# protomega.net
KiCad netlist of a schematic drawn in EAGLE
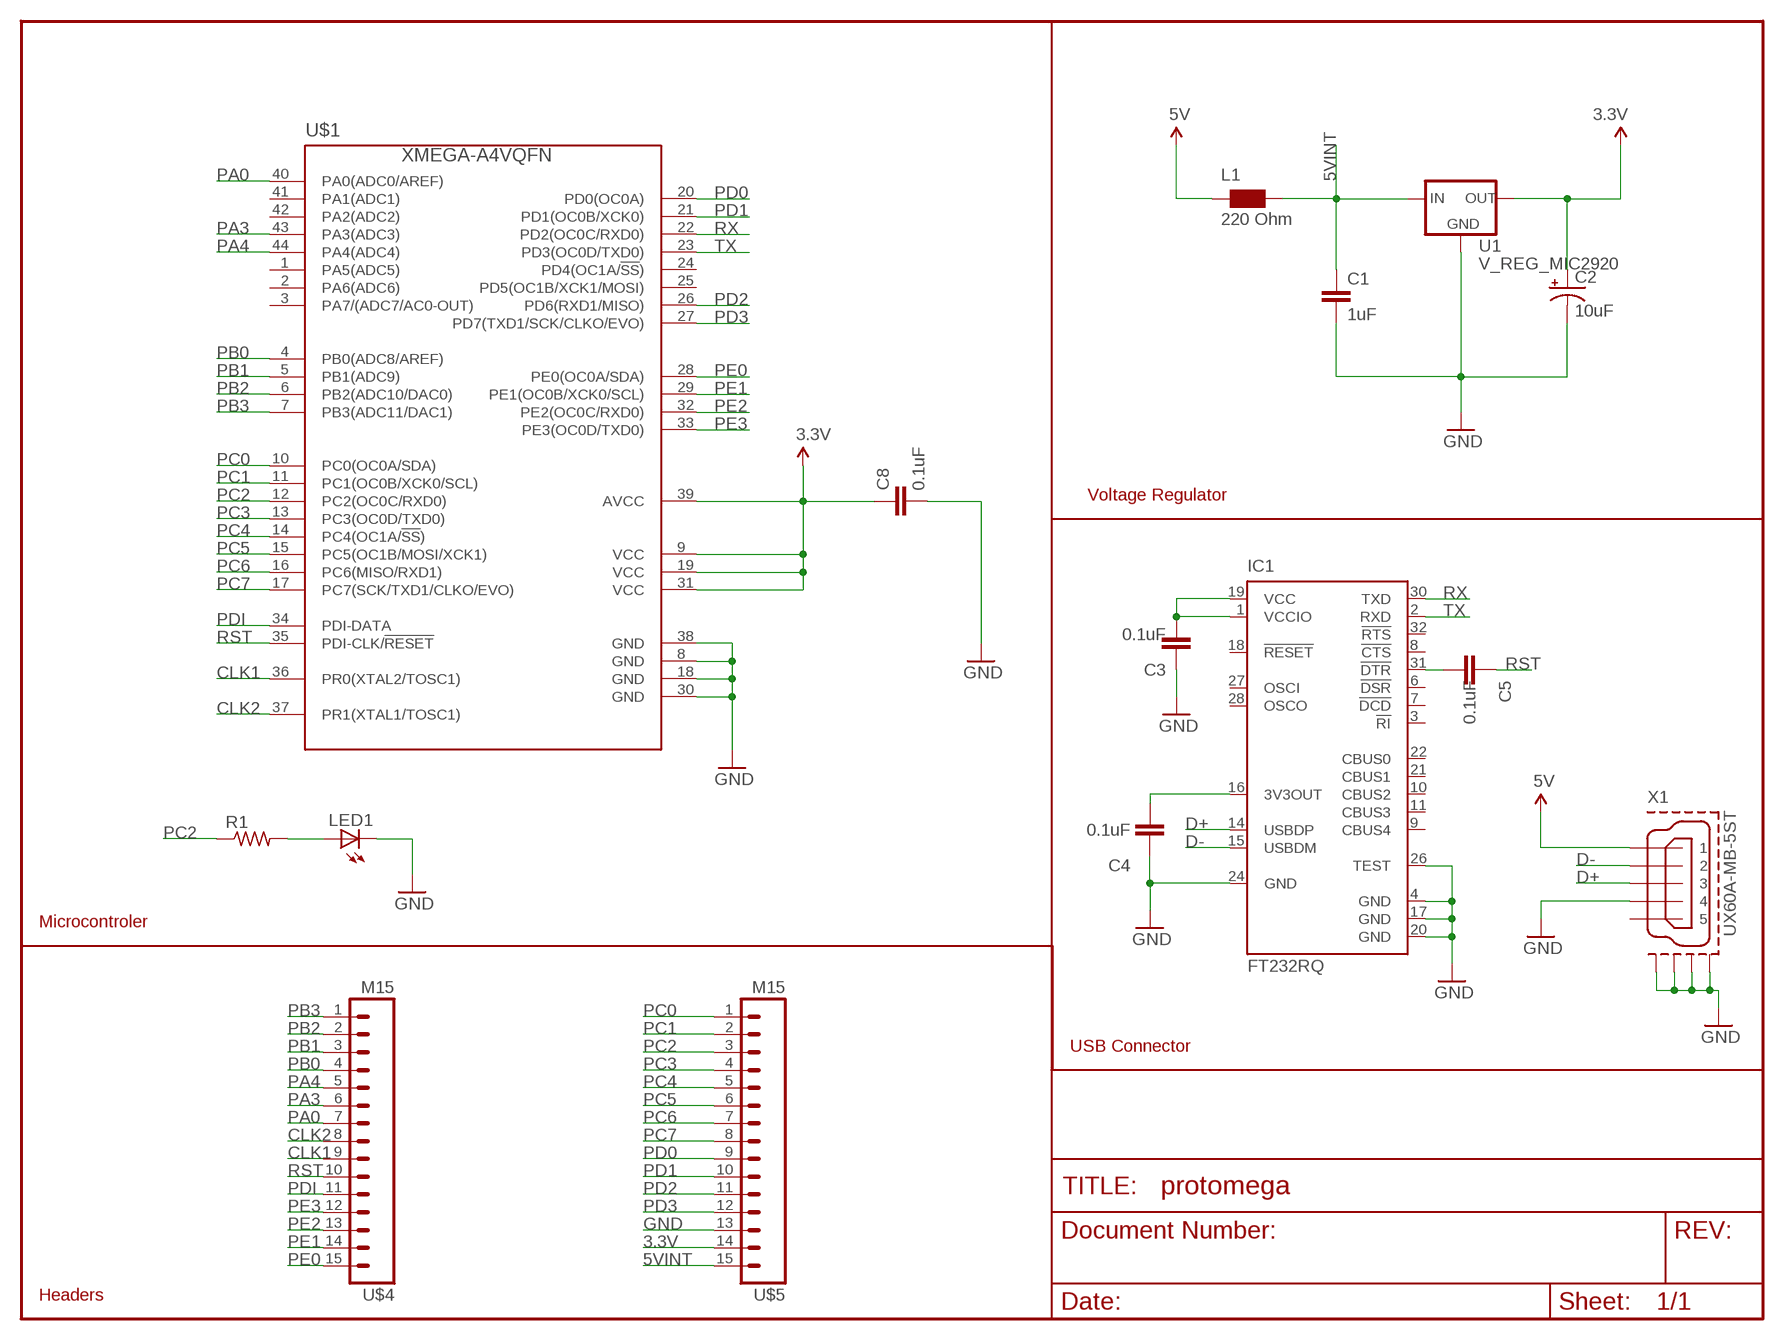
[diagram p0: schematic, sheet 1]

(export (version "E")
  (design (tool "Eeschema 10.0.6"))
  (components
    (comp (ref "C1")
      (value "1uF")
      (footprint "eagle-import:C0603")
      (libsource (lib "eagle-import") (part "C-EUC0603"))
    )
    (comp (ref "C2")
      (value "10uF")
      (footprint "eagle-import:EIA3216")
      (libsource (lib "eagle-import") (part "CAP_POL1206"))
    )
    (comp (ref "C3")
      (value "0.1uF")
      (footprint "eagle-import:C0603")
      (libsource (lib "eagle-import") (part "C-EUC0603"))
    )
    (comp (ref "C4")
      (value "0.1uF")
      (footprint "eagle-import:C0603")
      (libsource (lib "eagle-import") (part "C-EUC0603"))
    )
    (comp (ref "C5")
      (value "0.1uF")
      (footprint "eagle-import:C0603")
      (libsource (lib "eagle-import") (part "C-EUC0603"))
    )
    (comp (ref "C8")
      (value "0.1uF")
      (footprint "eagle-import:C0603")
      (libsource (lib "eagle-import") (part "C-EUC0603"))
    )
    (comp (ref "IC1")
      (value "FT232RQ")
      (footprint "eagle-import:QFN32")
      (libsource (lib "eagle-import") (part "FT232RQ"))
    )
    (comp (ref "L1")
      (value "220 Ohm")
      (footprint "eagle-import:0603")
      (libsource (lib "eagle-import") (part "WE-CBF_0603"))
    )
    (comp (ref "LED1")
      (value "LEDSMT1206")
      (footprint "eagle-import:1206")
      (libsource (lib "eagle-import") (part "LEDSMT1206"))
    )
    (comp (ref "R1")
      (value "R-US_R0603")
      (footprint "eagle-import:R0603")
      (libsource (lib "eagle-import") (part "R-US_R0603"))
    )
    (comp (ref "U$1")
      (value "XMEGA-A4VQFN")
      (footprint "eagle-import:QFN44")
      (libsource (lib "eagle-import") (part "XMEGA-A4VQFN"))
    )
    (comp (ref "U$4")
      (value "M15")
      (footprint "eagle-import:1X15")
      (libsource (lib "eagle-import") (part "M15"))
    )
    (comp (ref "U$5")
      (value "M15")
      (footprint "eagle-import:1X15")
      (libsource (lib "eagle-import") (part "M15"))
    )
    (comp (ref "U1")
      (value "V_REG_MIC2920")
      (footprint "eagle-import:SOT223")
      (libsource (lib "eagle-import") (part "V_REG_MIC2920"))
    )
    (comp (ref "X1")
      (value "UX60A-MB-5ST")
      (footprint "eagle-import:UX60A-MB-5ST")
      (libsource (lib "eagle-import") (part "MINI-USB-SHIELD-UX60A-MB-5ST"))
    )
  )
  (nets
    (net (code "1") (name "/5VINT") (class "Default")
      (node (ref "C1") (pin "1") (pinfunction "1_1") (pintype "passive"))
      (node (ref "L1") (pin "2") (pinfunction "2_2") (pintype "passive"))
      (node (ref "U$5") (pin "15") (pinfunction "15_15") (pintype "passive"))
      (node (ref "U1") (pin "1") (pinfunction "IN_1") (pintype "input"))
    )
    (net (code "2") (name "/CLK1") (class "Default")
      (node (ref "U$1") (pin "36") (pinfunction "PR0(XTAL2/TOSC1)_36") (pintype "bidirectional"))
      (node (ref "U$4") (pin "9") (pinfunction "9_9") (pintype "passive"))
    )
    (net (code "3") (name "/CLK2") (class "Default")
      (node (ref "U$1") (pin "37") (pinfunction "PR1(XTAL1/TOSC1)_37") (pintype "bidirectional"))
      (node (ref "U$4") (pin "8") (pinfunction "8_8") (pintype "passive"))
    )
    (net (code "4") (name "/D+") (class "Default")
      (node (ref "IC1") (pin "14") (pinfunction "USBDP_14") (pintype "bidirectional"))
      (node (ref "X1") (pin "3") (pinfunction "3_3") (pintype "input"))
    )
    (net (code "5") (name "/D-") (class "Default")
      (node (ref "IC1") (pin "15") (pinfunction "USBDM_15") (pintype "bidirectional"))
      (node (ref "X1") (pin "2") (pinfunction "2_2") (pintype "input"))
    )
    (net (code "6") (name "/PA0") (class "Default")
      (node (ref "U$1") (pin "40") (pinfunction "PA0(ADC0/AREF)_40") (pintype "bidirectional"))
      (node (ref "U$4") (pin "7") (pinfunction "7_7") (pintype "passive"))
    )
    (net (code "7") (name "/PA3") (class "Default")
      (node (ref "U$1") (pin "43") (pinfunction "PA3(ADC3)_43") (pintype "bidirectional"))
      (node (ref "U$4") (pin "6") (pinfunction "6_6") (pintype "passive"))
    )
    (net (code "8") (name "/PA4") (class "Default")
      (node (ref "U$1") (pin "44") (pinfunction "PA4(ADC4)_44") (pintype "bidirectional"))
      (node (ref "U$4") (pin "5") (pinfunction "5_5") (pintype "passive"))
    )
    (net (code "9") (name "/PB0") (class "Default")
      (node (ref "U$1") (pin "4") (pinfunction "PB0(ADC8/AREF)_4") (pintype "bidirectional"))
      (node (ref "U$4") (pin "4") (pinfunction "4_4") (pintype "passive"))
    )
    (net (code "10") (name "/PB1") (class "Default")
      (node (ref "U$1") (pin "5") (pinfunction "PB1(ADC9)_5") (pintype "bidirectional"))
      (node (ref "U$4") (pin "3") (pinfunction "3_3") (pintype "passive"))
    )
    (net (code "11") (name "/PB2") (class "Default")
      (node (ref "U$1") (pin "6") (pinfunction "PB2(ADC10/DAC0)_6") (pintype "bidirectional"))
      (node (ref "U$4") (pin "2") (pinfunction "2_2") (pintype "passive"))
    )
    (net (code "12") (name "/PB3") (class "Default")
      (node (ref "U$1") (pin "7") (pinfunction "PB3(ADC11/DAC1)_7") (pintype "bidirectional"))
      (node (ref "U$4") (pin "1") (pinfunction "1_1") (pintype "passive"))
    )
    (net (code "13") (name "/PC0") (class "Default")
      (node (ref "U$1") (pin "10") (pinfunction "PC0(OC0A/SDA)_10") (pintype "bidirectional"))
      (node (ref "U$5") (pin "1") (pinfunction "1_1") (pintype "passive"))
    )
    (net (code "14") (name "/PC1") (class "Default")
      (node (ref "U$1") (pin "11") (pinfunction "PC1(OC0B/XCK0/SCL)_11") (pintype "bidirectional"))
      (node (ref "U$5") (pin "2") (pinfunction "2_2") (pintype "passive"))
    )
    (net (code "15") (name "/PC2") (class "Default")
      (node (ref "R1") (pin "1") (pinfunction "1_1") (pintype "passive"))
      (node (ref "U$1") (pin "12") (pinfunction "PC2(OC0C/RXD0)_12") (pintype "bidirectional"))
      (node (ref "U$5") (pin "3") (pinfunction "3_3") (pintype "passive"))
    )
    (net (code "16") (name "/PC3") (class "Default")
      (node (ref "U$1") (pin "13") (pinfunction "PC3(OC0D/TXD0)_13") (pintype "bidirectional"))
      (node (ref "U$5") (pin "4") (pinfunction "4_4") (pintype "passive"))
    )
    (net (code "17") (name "/PC4") (class "Default")
      (node (ref "U$1") (pin "14") (pinfunction "PC4(OC1A/~{SS})_14") (pintype "bidirectional"))
      (node (ref "U$5") (pin "5") (pinfunction "5_5") (pintype "passive"))
    )
    (net (code "18") (name "/PC5") (class "Default")
      (node (ref "U$1") (pin "15") (pinfunction "PC5(OC1B/MOSI/XCK1)_15") (pintype "bidirectional"))
      (node (ref "U$5") (pin "6") (pinfunction "6_6") (pintype "passive"))
    )
    (net (code "19") (name "/PC6") (class "Default")
      (node (ref "U$1") (pin "16") (pinfunction "PC6(MISO/RXD1)_16") (pintype "bidirectional"))
      (node (ref "U$5") (pin "7") (pinfunction "7_7") (pintype "passive"))
    )
    (net (code "20") (name "/PC7") (class "Default")
      (node (ref "U$1") (pin "17") (pinfunction "PC7(SCK/TXD1/CLKO/EVO)_17") (pintype "bidirectional"))
      (node (ref "U$5") (pin "8") (pinfunction "8_8") (pintype "passive"))
    )
    (net (code "21") (name "/PD0") (class "Default")
      (node (ref "U$1") (pin "20") (pinfunction "PD0(OC0A)_20") (pintype "bidirectional"))
      (node (ref "U$5") (pin "9") (pinfunction "9_9") (pintype "passive"))
    )
    (net (code "22") (name "/PD1") (class "Default")
      (node (ref "U$1") (pin "21") (pinfunction "PD1(OC0B/XCK0)_21") (pintype "bidirectional"))
      (node (ref "U$5") (pin "10") (pinfunction "10_10") (pintype "passive"))
    )
    (net (code "23") (name "/PD2") (class "Default")
      (node (ref "U$1") (pin "26") (pinfunction "PD6(RXD1/MISO)_26") (pintype "bidirectional"))
      (node (ref "U$5") (pin "11") (pinfunction "11_11") (pintype "passive"))
    )
    (net (code "24") (name "/PD3") (class "Default")
      (node (ref "U$1") (pin "27") (pinfunction "PD7(TXD1/SCK/CLKO/EVO)_27") (pintype "bidirectional"))
      (node (ref "U$5") (pin "12") (pinfunction "12_12") (pintype "passive"))
    )
    (net (code "25") (name "/PDI") (class "Default")
      (node (ref "U$1") (pin "34") (pinfunction "PDI-DATA_34") (pintype "bidirectional"))
      (node (ref "U$4") (pin "11") (pinfunction "11_11") (pintype "passive"))
    )
    (net (code "26") (name "/PE0") (class "Default")
      (node (ref "U$1") (pin "28") (pinfunction "PE0(OC0A/SDA)_28") (pintype "bidirectional"))
      (node (ref "U$4") (pin "15") (pinfunction "15_15") (pintype "passive"))
    )
    (net (code "27") (name "/PE1") (class "Default")
      (node (ref "U$1") (pin "29") (pinfunction "PE1(OC0B/XCK0/SCL)_29") (pintype "bidirectional"))
      (node (ref "U$4") (pin "14") (pinfunction "14_14") (pintype "passive"))
    )
    (net (code "28") (name "/PE2") (class "Default")
      (node (ref "U$1") (pin "32") (pinfunction "PE2(OC0C/RXD0)_32") (pintype "bidirectional"))
      (node (ref "U$4") (pin "13") (pinfunction "13_13") (pintype "passive"))
    )
    (net (code "29") (name "/PE3") (class "Default")
      (node (ref "U$1") (pin "33") (pinfunction "PE3(OC0D/TXD0)_33") (pintype "bidirectional"))
      (node (ref "U$4") (pin "12") (pinfunction "12_12") (pintype "passive"))
    )
    (net (code "30") (name "/RST") (class "Default")
      (node (ref "C5") (pin "1") (pinfunction "1_1") (pintype "passive"))
      (node (ref "U$1") (pin "35") (pinfunction "PDI-CLK/~{RESET}_35") (pintype "input"))
      (node (ref "U$4") (pin "10") (pinfunction "10_10") (pintype "passive"))
    )
    (net (code "31") (name "/RX") (class "Default")
      (node (ref "IC1") (pin "30") (pinfunction "TXD_30") (pintype "output"))
      (node (ref "U$1") (pin "22") (pinfunction "PD2(OC0C/RXD0)_22") (pintype "bidirectional"))
    )
    (net (code "32") (name "/TX") (class "Default")
      (node (ref "IC1") (pin "2") (pinfunction "RXD_2") (pintype "input"))
      (node (ref "U$1") (pin "23") (pinfunction "PD3(OC0D/TXD0)_23") (pintype "bidirectional"))
    )
    (net (code "33") (name "3.3V") (class "Default")
      (node (ref "C2") (pin "A") (pinfunction "+_A") (pintype "passive"))
      (node (ref "C8") (pin "1") (pinfunction "1_1") (pintype "passive"))
      (node (ref "U$1") (pin "19") (pinfunction "VCC_19") (pintype "power_in"))
      (node (ref "U$1") (pin "31") (pinfunction "VCC_31") (pintype "power_in"))
      (node (ref "U$1") (pin "39") (pinfunction "AVCC_39") (pintype "power_in"))
      (node (ref "U$1") (pin "9") (pinfunction "VCC_9") (pintype "power_in"))
      (node (ref "U$5") (pin "14") (pinfunction "14_14") (pintype "passive"))
      (node (ref "U1") (pin "3") (pinfunction "OUT_3") (pintype "output"))
    )
    (net (code "34") (name "5V") (class "Default")
      (node (ref "L1") (pin "1") (pinfunction "1_1") (pintype "passive"))
      (node (ref "X1") (pin "1") (pinfunction "1_1") (pintype "input"))
    )
    (net (code "35") (name "GND") (class "Default")
      (node (ref "C1") (pin "2") (pinfunction "2_2") (pintype "passive"))
      (node (ref "C2") (pin "C") (pinfunction "-_C") (pintype "passive"))
      (node (ref "C3") (pin "1") (pinfunction "1_1") (pintype "passive"))
      (node (ref "C4") (pin "1") (pinfunction "1_1") (pintype "passive"))
      (node (ref "C8") (pin "2") (pinfunction "2_2") (pintype "passive"))
      (node (ref "IC1") (pin "17") (pinfunction "GND_17") (pintype "power_in"))
      (node (ref "IC1") (pin "20") (pinfunction "GND_20") (pintype "power_in"))
      (node (ref "IC1") (pin "24") (pinfunction "GND_24") (pintype "power_in"))
      (node (ref "IC1") (pin "26") (pinfunction "TEST_26") (pintype "input"))
      (node (ref "IC1") (pin "4") (pinfunction "GND_4") (pintype "power_in"))
      (node (ref "LED1") (pin "C") (pinfunction "C_C") (pintype "passive"))
      (node (ref "U$1") (pin "18") (pinfunction "GND_18") (pintype "power_in"))
      (node (ref "U$1") (pin "30") (pinfunction "GND_30") (pintype "power_in"))
      (node (ref "U$1") (pin "38") (pinfunction "GND_38") (pintype "power_in"))
      (node (ref "U$1") (pin "8") (pinfunction "GND_8") (pintype "power_in"))
      (node (ref "U$5") (pin "13") (pinfunction "13_13") (pintype "passive"))
      (node (ref "U1") (pin "2") (pinfunction "GND_2") (pintype "input"))
      (node (ref "X1") (pin "4") (pinfunction "4_4") (pintype "input"))
      (node (ref "X1") (pin "M1") (pinfunction "GND1_M1") (pintype "bidirectional"))
      (node (ref "X1") (pin "M2") (pinfunction "GND2_M2") (pintype "bidirectional"))
      (node (ref "X1") (pin "M3") (pinfunction "GND3_M3") (pintype "bidirectional"))
      (node (ref "X1") (pin "M4") (pinfunction "GND4_M4") (pintype "bidirectional"))
    )
    (net (code "36") (name "Net-(IC1-3V3OUT)") (class "Default")
      (node (ref "C4") (pin "2") (pinfunction "2_2") (pintype "passive"))
      (node (ref "IC1") (pin "16") (pinfunction "3V3OUT_16") (pintype "output"))
    )
    (net (code "37") (name "Net-(IC1-VCC)") (class "Default")
      (node (ref "C3") (pin "2") (pinfunction "2_2") (pintype "passive"))
      (node (ref "IC1") (pin "1") (pinfunction "VCCIO_1") (pintype "power_in"))
      (node (ref "IC1") (pin "19") (pinfunction "VCC_19") (pintype "power_in"))
    )
    (net (code "38") (name "Net-(IC1-~{DTR})") (class "Default")
      (node (ref "C5") (pin "2") (pinfunction "2_2") (pintype "passive"))
      (node (ref "IC1") (pin "31") (pinfunction "~{DTR}_31") (pintype "output"))
    )
    (net (code "39") (name "Net-(LED1-PadA)") (class "Default")
      (node (ref "LED1") (pin "A") (pinfunction "A_A") (pintype "passive"))
      (node (ref "R1") (pin "2") (pinfunction "2_2") (pintype "passive"))
    )
    (net (code "40") (name "unconnected-(IC1-CBUS0-Pad22)") (class "Default")
      (node (ref "IC1") (pin "22") (pinfunction "CBUS0_22") (pintype "bidirectional"))
    )
    (net (code "41") (name "unconnected-(IC1-CBUS1-Pad21)") (class "Default")
      (node (ref "IC1") (pin "21") (pinfunction "CBUS1_21") (pintype "bidirectional"))
    )
    (net (code "42") (name "unconnected-(IC1-CBUS2-Pad10)") (class "Default")
      (node (ref "IC1") (pin "10") (pinfunction "CBUS2_10") (pintype "bidirectional"))
    )
    (net (code "43") (name "unconnected-(IC1-CBUS3-Pad11)") (class "Default")
      (node (ref "IC1") (pin "11") (pinfunction "CBUS3_11") (pintype "bidirectional"))
    )
    (net (code "44") (name "unconnected-(IC1-CBUS4-Pad9)") (class "Default")
      (node (ref "IC1") (pin "9") (pinfunction "CBUS4_9") (pintype "bidirectional"))
    )
    (net (code "45") (name "unconnected-(IC1-OSCI-Pad27)") (class "Default")
      (node (ref "IC1") (pin "27") (pinfunction "OSCI_27") (pintype "input"))
    )
    (net (code "46") (name "unconnected-(IC1-OSCO-Pad28)") (class "Default")
      (node (ref "IC1") (pin "28") (pinfunction "OSCO_28") (pintype "output"))
    )
    (net (code "47") (name "unconnected-(IC1-~{CTS}-Pad8)") (class "Default")
      (node (ref "IC1") (pin "8") (pinfunction "~{CTS}_8") (pintype "input"))
    )
    (net (code "48") (name "unconnected-(IC1-~{DCD}-Pad7)") (class "Default")
      (node (ref "IC1") (pin "7") (pinfunction "~{DCD}_7") (pintype "input"))
    )
    (net (code "49") (name "unconnected-(IC1-~{DSR}-Pad6)") (class "Default")
      (node (ref "IC1") (pin "6") (pinfunction "~{DSR}_6") (pintype "input"))
    )
    (net (code "50") (name "unconnected-(IC1-~{RESET}-Pad18)") (class "Default")
      (node (ref "IC1") (pin "18") (pinfunction "~{RESET}_18") (pintype "input"))
    )
    (net (code "51") (name "unconnected-(IC1-~{RI}-Pad3)") (class "Default")
      (node (ref "IC1") (pin "3") (pinfunction "~{RI}_3") (pintype "input"))
    )
    (net (code "52") (name "unconnected-(IC1-~{RTS}-Pad32)") (class "Default")
      (node (ref "IC1") (pin "32") (pinfunction "~{RTS}_32") (pintype "output"))
    )
    (net (code "53") (name "unconnected-(U$1-PA1(ADC1)-Pad41)") (class "Default")
      (node (ref "U$1") (pin "41") (pinfunction "PA1(ADC1)_41") (pintype "bidirectional"))
    )
    (net (code "54") (name "unconnected-(U$1-PA2(ADC2)-Pad42)") (class "Default")
      (node (ref "U$1") (pin "42") (pinfunction "PA2(ADC2)_42") (pintype "bidirectional"))
    )
    (net (code "55") (name "unconnected-(U$1-PA5(ADC5)-Pad1)") (class "Default")
      (node (ref "U$1") (pin "1") (pinfunction "PA5(ADC5)_1") (pintype "bidirectional"))
    )
    (net (code "56") (name "unconnected-(U$1-PA6(ADC6)-Pad2)") (class "Default")
      (node (ref "U$1") (pin "2") (pinfunction "PA6(ADC6)_2") (pintype "bidirectional"))
    )
    (net (code "57") (name "unconnected-(U$1-PA7{slash}(ADC7{slash}AC0-OUT)-Pad3)") (class "Default")
      (node (ref "U$1") (pin "3") (pinfunction "PA7/(ADC7/AC0-OUT)_3") (pintype "bidirectional"))
    )
    (net (code "58") (name "unconnected-(U$1-PD4(OC1A{slash}~{SS})-Pad24)") (class "Default")
      (node (ref "U$1") (pin "24") (pinfunction "PD4(OC1A/~{SS})_24") (pintype "bidirectional"))
    )
    (net (code "59") (name "unconnected-(U$1-PD5(OC1B{slash}XCK1{slash}MOSI)-Pad25)") (class "Default")
      (node (ref "U$1") (pin "25") (pinfunction "PD5(OC1B/XCK1/MOSI)_25") (pintype "bidirectional"))
    )
    (net (code "60") (name "unconnected-(X1-Pad5)") (class "Default")
      (node (ref "X1") (pin "5") (pinfunction "5_5") (pintype "input"))
    )
  )
)
